# LAB-ASDM300F.net
KiCad netlist of a schematic drawn in EAGLE
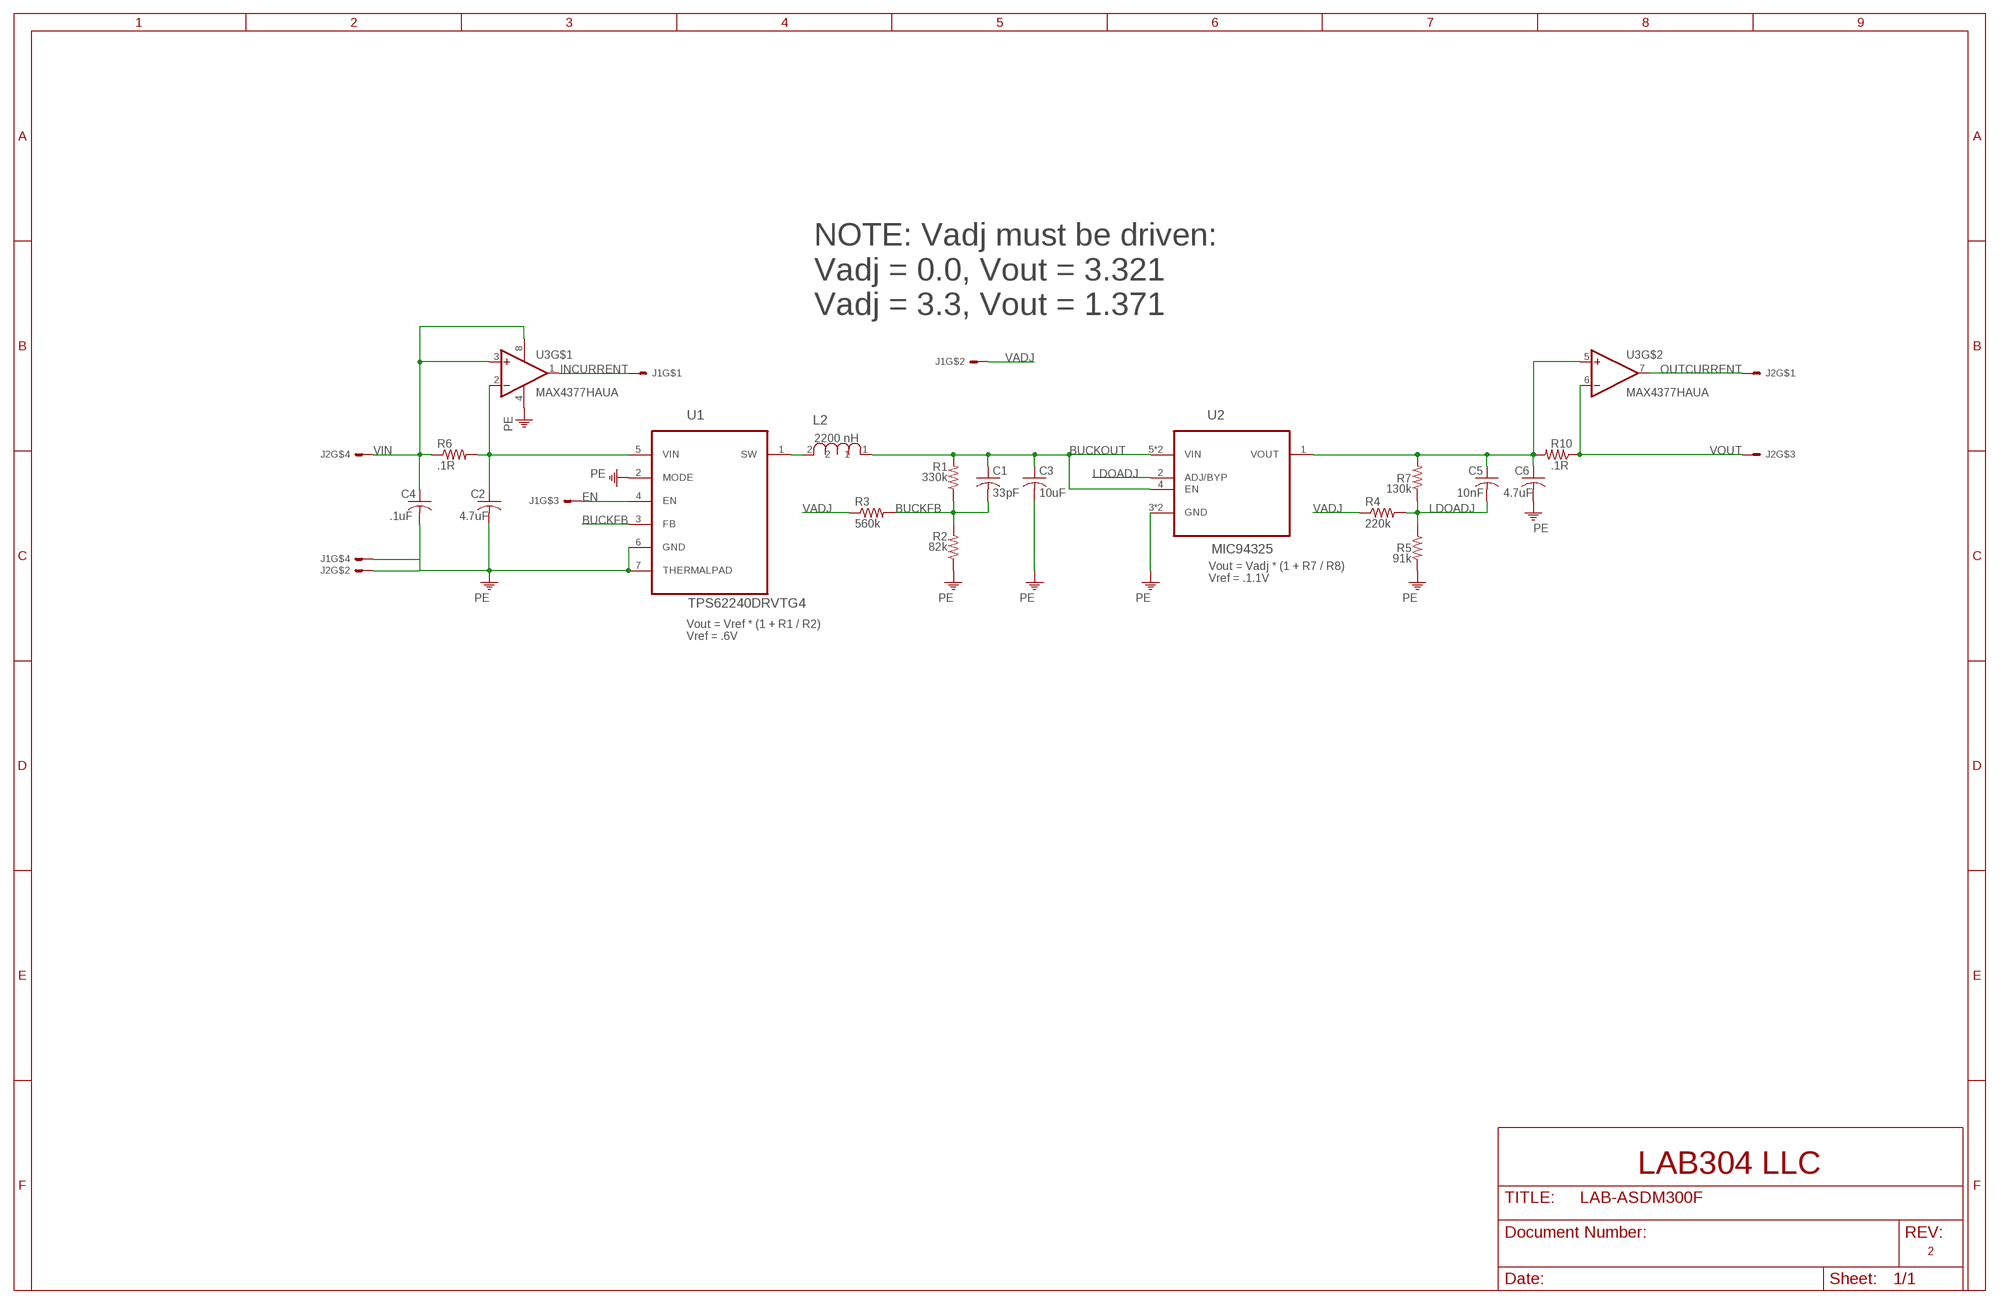
[diagram p0: schematic, sheet 1]

(export (version "E")
  (design (tool "Eeschema 10.0.6"))
  (components
    (comp (ref "C1")
      (value "33pF")
      (footprint "eagle-import:C0603")
      (libsource (lib "eagle-import") (part "C-USC0603"))
    )
    (comp (ref "C2")
      (value "4.7uF")
      (footprint "eagle-import:C0603")
      (libsource (lib "eagle-import") (part "C-USC0603"))
    )
    (comp (ref "C3")
      (value "10uF")
      (footprint "eagle-import:C0603")
      (libsource (lib "eagle-import") (part "C-USC0603"))
    )
    (comp (ref "C4")
      (value ".1uF")
      (footprint "eagle-import:C0603")
      (libsource (lib "eagle-import") (part "C-USC0603"))
    )
    (comp (ref "C5")
      (value "10nF")
      (footprint "eagle-import:C0603")
      (libsource (lib "eagle-import") (part "C-USC0603"))
    )
    (comp (ref "C6")
      (value "4.7uF")
      (footprint "eagle-import:C0603")
      (libsource (lib "eagle-import") (part "C-USC0603"))
    )
    (comp (ref "J1")
      (value "SULLINSSMTHEADER-4")
      (footprint "eagle-import:SMTHEADER-4")
      (libsource (lib "eagle-import") (part "SULLINSSMTHEADER-4"))
    )
    (comp (ref "J2")
      (value "SULLINSSMTHEADER-4")
      (footprint "eagle-import:SMTHEADER-4")
      (libsource (lib "eagle-import") (part "SULLINSSMTHEADER-4"))
    )
    (comp (ref "L2")
      (value "2200 nH")
      (footprint "eagle-import:INDC2520X18N")
      (fields (field (name "MPN") "PM1008-2R2K-RC") (field (name "TOLERANCE") "±10 %"))
      (libsource (lib "eagle-import") (part "PM1008-2R2K-RC"))
    )
    (comp (ref "R1")
      (value "330k")
      (footprint "eagle-import:R0603")
      (libsource (lib "eagle-import") (part "R-US_R0603"))
    )
    (comp (ref "R2")
      (value "82k")
      (footprint "eagle-import:R0603")
      (libsource (lib "eagle-import") (part "R-US_R0603"))
    )
    (comp (ref "R3")
      (value "560k")
      (footprint "eagle-import:R0603")
      (libsource (lib "eagle-import") (part "R-US_R0603"))
    )
    (comp (ref "R4")
      (value "220k")
      (footprint "eagle-import:R0603")
      (libsource (lib "eagle-import") (part "R-US_R0603"))
    )
    (comp (ref "R5")
      (value "91k")
      (footprint "eagle-import:R0603")
      (libsource (lib "eagle-import") (part "R-US_R0603"))
    )
    (comp (ref "R6")
      (value ".1R")
      (footprint "eagle-import:R0603")
      (libsource (lib "eagle-import") (part "R-US_R0603"))
    )
    (comp (ref "R7")
      (value "130k")
      (footprint "eagle-import:R0603")
      (libsource (lib "eagle-import") (part "R-US_R0603"))
    )
    (comp (ref "R10")
      (value ".1R")
      (footprint "eagle-import:R0603")
      (libsource (lib "eagle-import") (part "R-US_R0603"))
    )
    (comp (ref "U1")
      (value "TPS62240DRVTG4")
      (footprint "eagle-import:SON65P210X210X80-7N")
      (libsource (lib "eagle-import") (part "TPS62240DRVTG4"))
    )
    (comp (ref "U2")
      (value "MIC94325")
      (footprint "eagle-import:SON65P160X160X80-7N")
      (libsource (lib "eagle-import") (part "MIC94325"))
    )
    (comp (ref "U3")
      (value "MAX4377HAUA")
      (footprint "eagle-import:UMAX8")
      (libsource (lib "eagle-import") (part "MAX4377"))
    )
  )
  (nets
    (net (code "1") (name "/BUCKFB") (class "Default")
      (node (ref "C1") (pin "2") (pinfunction "2_2") (pintype "passive"))
      (node (ref "R1") (pin "1") (pinfunction "1_1") (pintype "passive"))
      (node (ref "R2") (pin "2") (pinfunction "2_2") (pintype "passive"))
      (node (ref "R3") (pin "2") (pinfunction "2_2") (pintype "passive"))
      (node (ref "U1") (pin "3") (pinfunction "FB_3") (pintype "input"))
    )
    (net (code "2") (name "/BUCKOUT") (class "Default")
      (node (ref "C1") (pin "1") (pinfunction "1_1") (pintype "passive"))
      (node (ref "C3") (pin "1") (pinfunction "1_1") (pintype "passive"))
      (node (ref "L2") (pin "1") (pinfunction "1_1") (pintype "passive"))
      (node (ref "R1") (pin "2") (pinfunction "2_2") (pintype "passive"))
      (node (ref "U2") (pin "4") (pinfunction "EN_4") (pintype "input"))
      (node (ref "U2") (pin "5") (pinfunction "VIN_5") (pintype "power_in"))
      (node (ref "U2") (pin "6") (pinfunction "VIN_6") (pintype "power_in"))
    )
    (net (code "3") (name "/EN") (class "Default")
      (node (ref "J1") (pin "P$3") (pinfunction "S_P$3") (pintype "passive"))
      (node (ref "U1") (pin "4") (pinfunction "EN_4") (pintype "input"))
    )
    (net (code "4") (name "/INCURRENT") (class "Default")
      (node (ref "J1") (pin "P$1") (pinfunction "S_P$1") (pintype "passive"))
      (node (ref "U3") (pin "1") (pinfunction "OUT_1") (pintype "output"))
    )
    (net (code "5") (name "/LDOADJ") (class "Default")
      (node (ref "C5") (pin "2") (pinfunction "2_2") (pintype "passive"))
      (node (ref "R4") (pin "2") (pinfunction "2_2") (pintype "passive"))
      (node (ref "R5") (pin "1") (pinfunction "1_1") (pintype "passive"))
      (node (ref "R7") (pin "1") (pinfunction "1_1") (pintype "passive"))
      (node (ref "U2") (pin "2") (pinfunction "ADJ/BYP_2") (pintype "input"))
    )
    (net (code "6") (name "/OUTCURRENT") (class "Default")
      (node (ref "J2") (pin "P$1") (pinfunction "S_P$1") (pintype "passive"))
      (node (ref "U3") (pin "7") (pinfunction "OUT_7") (pintype "output"))
    )
    (net (code "7") (name "/VADJ") (class "Default")
      (node (ref "J1") (pin "P$2") (pinfunction "S_P$2") (pintype "passive"))
      (node (ref "R3") (pin "1") (pinfunction "1_1") (pintype "passive"))
      (node (ref "R4") (pin "1") (pinfunction "1_1") (pintype "passive"))
    )
    (net (code "8") (name "/VIN") (class "Default")
      (node (ref "C4") (pin "1") (pinfunction "1_1") (pintype "passive"))
      (node (ref "J2") (pin "P$4") (pinfunction "S_P$4") (pintype "passive"))
      (node (ref "R6") (pin "1") (pinfunction "1_1") (pintype "passive"))
      (node (ref "U3") (pin "3") (pinfunction "+IN_3") (pintype "input"))
      (node (ref "U3") (pin "8") (pinfunction "V+_8") (pintype "power_in"))
    )
    (net (code "9") (name "/VOUT") (class "Default")
      (node (ref "J2") (pin "P$3") (pinfunction "S_P$3") (pintype "passive"))
      (node (ref "R10") (pin "1") (pinfunction "1_1") (pintype "passive"))
      (node (ref "U3") (pin "6") (pinfunction "-IN_6") (pintype "input"))
    )
    (net (code "10") (name "Net-(U1-SW)") (class "Default")
      (node (ref "L2") (pin "2") (pinfunction "2_2") (pintype "passive"))
      (node (ref "U1") (pin "1") (pinfunction "SW_1") (pintype "output"))
    )
    (net (code "11") (name "Net-(U1-VIN)") (class "Default")
      (node (ref "C2") (pin "1") (pinfunction "1_1") (pintype "passive"))
      (node (ref "R6") (pin "2") (pinfunction "2_2") (pintype "passive"))
      (node (ref "U1") (pin "5") (pinfunction "VIN_5") (pintype "power_in"))
      (node (ref "U3") (pin "2") (pinfunction "-IN_2") (pintype "input"))
    )
    (net (code "12") (name "Net-(U2-VOUT)") (class "Default")
      (node (ref "C5") (pin "1") (pinfunction "1_1") (pintype "passive"))
      (node (ref "C6") (pin "1") (pinfunction "1_1") (pintype "passive"))
      (node (ref "R10") (pin "2") (pinfunction "2_2") (pintype "passive"))
      (node (ref "R7") (pin "2") (pinfunction "2_2") (pintype "passive"))
      (node (ref "U2") (pin "1") (pinfunction "VOUT_1") (pintype "output"))
      (node (ref "U3") (pin "5") (pinfunction "+IN_5") (pintype "input"))
    )
    (net (code "13") (name "PE") (class "Default")
      (node (ref "C2") (pin "2") (pinfunction "2_2") (pintype "passive"))
      (node (ref "C3") (pin "2") (pinfunction "2_2") (pintype "passive"))
      (node (ref "C4") (pin "2") (pinfunction "2_2") (pintype "passive"))
      (node (ref "C6") (pin "2") (pinfunction "2_2") (pintype "passive"))
      (node (ref "J1") (pin "P$4") (pinfunction "S_P$4") (pintype "passive"))
      (node (ref "J2") (pin "P$2") (pinfunction "S_P$2") (pintype "passive"))
      (node (ref "R2") (pin "1") (pinfunction "1_1") (pintype "passive"))
      (node (ref "R5") (pin "2") (pinfunction "2_2") (pintype "passive"))
      (node (ref "U1") (pin "2") (pinfunction "MODE_2") (pintype "input"))
      (node (ref "U1") (pin "6") (pinfunction "GND_6") (pintype "passive"))
      (node (ref "U1") (pin "7") (pinfunction "THERMALPAD_7") (pintype "passive"))
      (node (ref "U2") (pin "3") (pinfunction "GND_3") (pintype "passive"))
      (node (ref "U2") (pin "7") (pinfunction "GND_7") (pintype "passive"))
      (node (ref "U3") (pin "4") (pinfunction "V-_4") (pintype "power_in"))
    )
  )
)
